# IOB-RR-CirKits.net
KiCad netlist of a schematic drawn in EAGLE
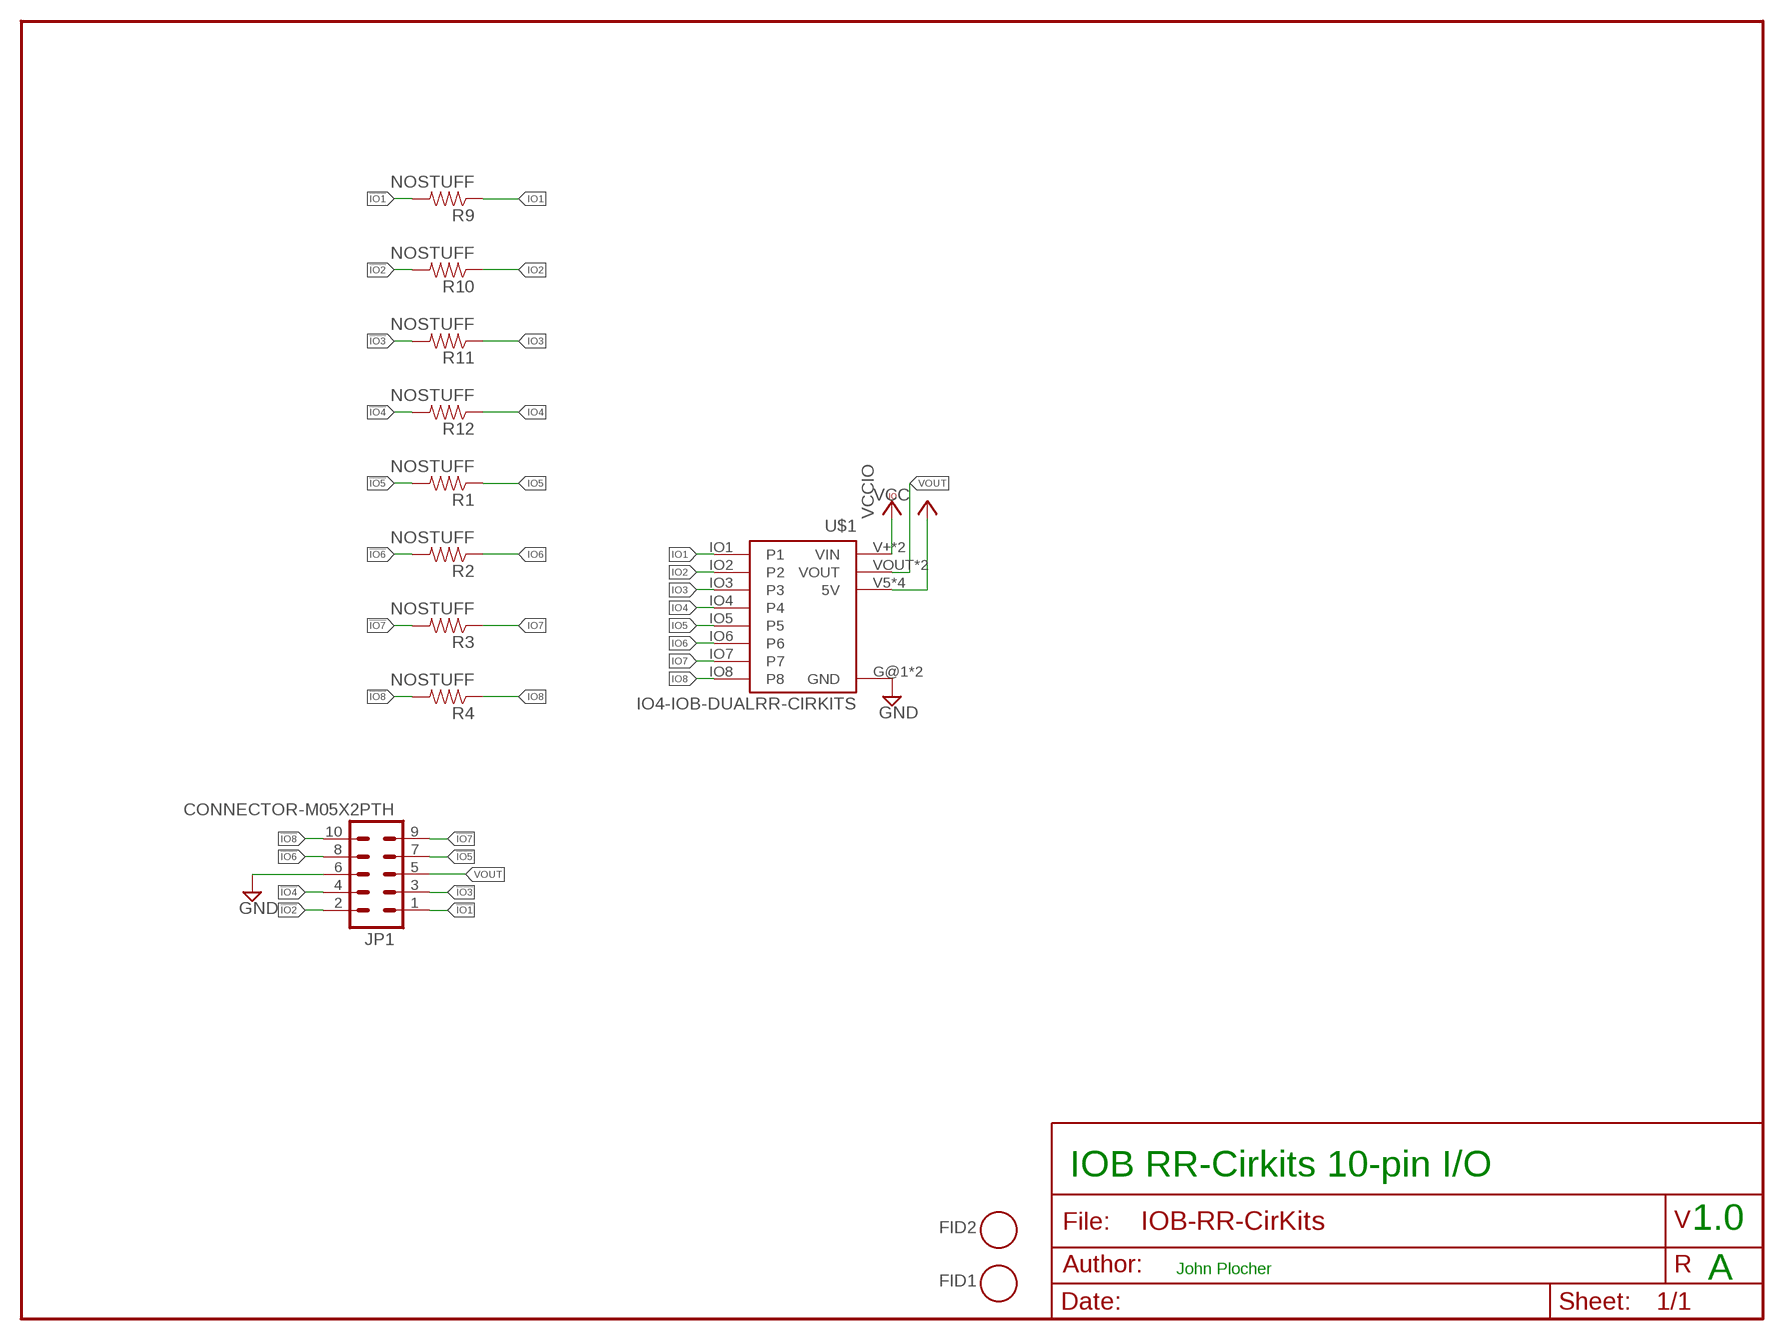
[diagram p0: schematic, sheet 1]

(export (version "E")
  (design (tool "Eeschema 10.0.6"))
  (components
    (comp (ref "FID1")
      (value "FIDUCIAL")
      (footprint "eagle-import:FIDUCIAL_1MM")
      (libsource (lib "eagle-import") (part "FIDUCIAL"))
    )
    (comp (ref "FID2")
      (value "FIDUCIAL")
      (footprint "eagle-import:FIDUCIAL_1MM")
      (libsource (lib "eagle-import") (part "FIDUCIAL"))
    )
    (comp (ref "JP1")
      (value "CONNECTOR-M05X2PTH")
      (footprint "eagle-import:AVR_ICSP")
      (libsource (lib "eagle-import") (part "CONNECTOR-M05X2PTH"))
    )
    (comp (ref "R1")
      (value "NOSTUFF")
      (footprint "eagle-import:CUT-R")
      (libsource (lib "eagle-import") (part "RPTH-R0"))
    )
    (comp (ref "R2")
      (value "NOSTUFF")
      (footprint "eagle-import:CUT-R")
      (libsource (lib "eagle-import") (part "RPTH-R0"))
    )
    (comp (ref "R3")
      (value "NOSTUFF")
      (footprint "eagle-import:CUT-R")
      (libsource (lib "eagle-import") (part "RPTH-R0"))
    )
    (comp (ref "R4")
      (value "NOSTUFF")
      (footprint "eagle-import:CUT-R")
      (libsource (lib "eagle-import") (part "RPTH-R0"))
    )
    (comp (ref "R9")
      (value "NOSTUFF")
      (footprint "eagle-import:CUT-R")
      (libsource (lib "eagle-import") (part "RPTH-R0"))
    )
    (comp (ref "R10")
      (value "NOSTUFF")
      (footprint "eagle-import:CUT-R")
      (libsource (lib "eagle-import") (part "RPTH-R0"))
    )
    (comp (ref "R11")
      (value "NOSTUFF")
      (footprint "eagle-import:CUT-R")
      (libsource (lib "eagle-import") (part "RPTH-R0"))
    )
    (comp (ref "R12")
      (value "NOSTUFF")
      (footprint "eagle-import:CUT-R")
      (libsource (lib "eagle-import") (part "RPTH-R0"))
    )
    (comp (ref "U$1")
      (value "IO4-IOB-DUALRR-CIRKITS")
      (footprint "eagle-import:10X-IOB")
      (libsource (lib "eagle-import") (part "IO4-IOB-DUALRR-CIRKITS"))
    )
  )
  (nets
    (net (code "1") (name "/~{IO1}") (class "Default")
      (node (ref "JP1") (pin "1") (pinfunction "1_1") (pintype "passive"))
      (node (ref "R9") (pin "P1") (pinfunction "2_P1") (pintype "passive"))
    )
    (net (code "2") (name "/~{IO2}") (class "Default")
      (node (ref "JP1") (pin "2") (pinfunction "2_2") (pintype "passive"))
      (node (ref "R10") (pin "P1") (pinfunction "2_P1") (pintype "passive"))
    )
    (net (code "3") (name "/~{IO3}") (class "Default")
      (node (ref "JP1") (pin "3") (pinfunction "3_3") (pintype "passive"))
      (node (ref "R11") (pin "P1") (pinfunction "2_P1") (pintype "passive"))
    )
    (net (code "4") (name "/~{IO4}") (class "Default")
      (node (ref "JP1") (pin "4") (pinfunction "4_4") (pintype "passive"))
      (node (ref "R12") (pin "P1") (pinfunction "2_P1") (pintype "passive"))
    )
    (net (code "5") (name "/~{IO5}") (class "Default")
      (node (ref "JP1") (pin "7") (pinfunction "7_7") (pintype "passive"))
      (node (ref "R1") (pin "P1") (pinfunction "2_P1") (pintype "passive"))
    )
    (net (code "6") (name "/~{IO6}") (class "Default")
      (node (ref "JP1") (pin "8") (pinfunction "8_8") (pintype "passive"))
      (node (ref "R2") (pin "P1") (pinfunction "2_P1") (pintype "passive"))
    )
    (net (code "7") (name "/~{IO7}") (class "Default")
      (node (ref "JP1") (pin "9") (pinfunction "9_9") (pintype "passive"))
      (node (ref "R3") (pin "P1") (pinfunction "2_P1") (pintype "passive"))
    )
    (net (code "8") (name "/~{IO8}") (class "Default")
      (node (ref "JP1") (pin "10") (pinfunction "10_10") (pintype "passive"))
      (node (ref "R4") (pin "P1") (pinfunction "2_P1") (pintype "passive"))
    )
    (net (code "9") (name "GND") (class "Default")
      (node (ref "JP1") (pin "6") (pinfunction "6_6") (pintype "passive"))
      (node (ref "U$1") (pin "G@1") (pinfunction "GND_G@1") (pintype "power_in"))
      (node (ref "U$1") (pin "G@3") (pinfunction "GND_G@3") (pintype "power_in"))
    )
    (net (code "10") (name "IO1") (class "Default")
      (node (ref "R9") (pin "P2") (pinfunction "1_P2") (pintype "passive"))
      (node (ref "U$1") (pin "IO1") (pinfunction "P1_IO1") (pintype "bidirectional"))
    )
    (net (code "11") (name "IO2") (class "Default")
      (node (ref "R10") (pin "P2") (pinfunction "1_P2") (pintype "passive"))
      (node (ref "U$1") (pin "IO2") (pinfunction "P2_IO2") (pintype "bidirectional"))
    )
    (net (code "12") (name "IO3") (class "Default")
      (node (ref "R11") (pin "P2") (pinfunction "1_P2") (pintype "passive"))
      (node (ref "U$1") (pin "IO3") (pinfunction "P3_IO3") (pintype "bidirectional"))
    )
    (net (code "13") (name "IO4") (class "Default")
      (node (ref "R12") (pin "P2") (pinfunction "1_P2") (pintype "passive"))
      (node (ref "U$1") (pin "IO4") (pinfunction "P4_IO4") (pintype "bidirectional"))
    )
    (net (code "14") (name "IO5") (class "Default")
      (node (ref "R1") (pin "P2") (pinfunction "1_P2") (pintype "passive"))
      (node (ref "U$1") (pin "IO5") (pinfunction "P5_IO5") (pintype "bidirectional"))
    )
    (net (code "15") (name "IO6") (class "Default")
      (node (ref "R2") (pin "P2") (pinfunction "1_P2") (pintype "passive"))
      (node (ref "U$1") (pin "IO6") (pinfunction "P6_IO6") (pintype "bidirectional"))
    )
    (net (code "16") (name "IO7") (class "Default")
      (node (ref "R3") (pin "P2") (pinfunction "1_P2") (pintype "passive"))
      (node (ref "U$1") (pin "IO7") (pinfunction "P7_IO7") (pintype "bidirectional"))
    )
    (net (code "17") (name "IO8") (class "Default")
      (node (ref "R4") (pin "P2") (pinfunction "1_P2") (pintype "passive"))
      (node (ref "U$1") (pin "IO8") (pinfunction "P8_IO8") (pintype "bidirectional"))
    )
    (net (code "18") (name "VCC") (class "Default")
      (node (ref "U$1") (pin "V5") (pinfunction "5V_V5") (pintype "power_in"))
      (node (ref "U$1") (pin "V5@1") (pinfunction "5V_V5@1") (pintype "power_in"))
      (node (ref "U$1") (pin "V5@2") (pinfunction "5V_V5@2") (pintype "power_in"))
      (node (ref "U$1") (pin "V5@3") (pinfunction "5V_V5@3") (pintype "power_in"))
    )
    (net (code "19") (name "VCCIO") (class "Default")
      (node (ref "U$1") (pin "V+") (pinfunction "VIN_V+") (pintype "power_in"))
      (node (ref "U$1") (pin "V+@1") (pinfunction "VIN_V+@1") (pintype "power_in"))
    )
    (net (code "20") (name "VOUT") (class "Default")
      (node (ref "JP1") (pin "5") (pinfunction "5_5") (pintype "passive"))
      (node (ref "U$1") (pin "VOUT") (pinfunction "VOUT_VOUT") (pintype "power_in"))
      (node (ref "U$1") (pin "VOUT@1") (pinfunction "VOUT_VOUT@1") (pintype "power_in"))
    )
  )
)
